# DWM.net
KiCad netlist of a schematic drawn in Altium Designer
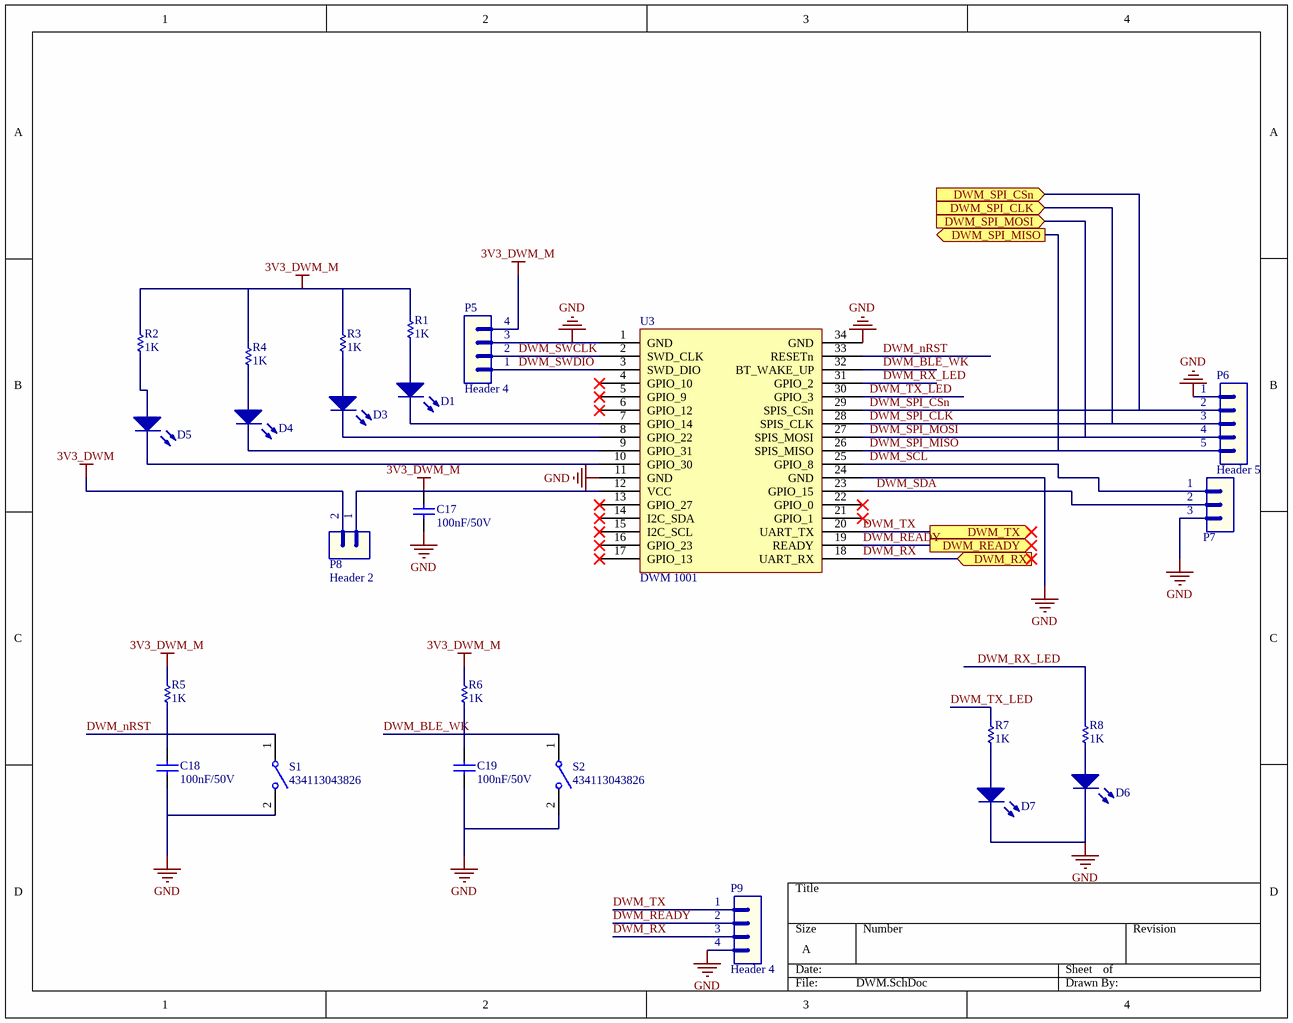
[diagram p0: DWM.SchDoc]

(export (version "E")
  (design (tool "Eeschema 10.0.6"))
  (components
    (comp (ref "C17")
      (value "100nF/50V")
      (footprint "CAP-SM-0805")
      (description "CAP CER 0.1UF 50V Y5V 0805")
      (fields
        (field (name "MANUFACTURER") "Samsung Electro-Mechanics")
        (field (name "MANUFACTURER PART NUMBER") "CL21F104ZBCNNNC")
      )
      (libsource (lib "Capacitor") (part "Cap-100nF-50V-0805"))
    )
    (comp (ref "C18")
      (value "100nF/50V")
      (footprint "CAP-SM-0805")
      (description "CAP CER 0.1UF 50V Y5V 0805")
      (fields
        (field (name "MANUFACTURER") "Samsung Electro-Mechanics")
        (field (name "MANUFACTURER PART NUMBER") "CL21F104ZBCNNNC")
      )
      (libsource (lib "Capacitor") (part "Cap-100nF-50V-0805"))
    )
    (comp (ref "C19")
      (value "100nF/50V")
      (footprint "CAP-SM-0805")
      (description "CAP CER 0.1UF 50V Y5V 0805")
      (fields
        (field (name "MANUFACTURER") "Samsung Electro-Mechanics")
        (field (name "MANUFACTURER PART NUMBER") "CL21F104ZBCNNNC")
      )
      (libsource (lib "Capacitor") (part "Cap-100nF-50V-0805"))
    )
    (comp (ref "D1")
      (value "LED")
      (footprint "LED_0805_Blue")
      (libsource (lib "PIF_C16_lib (1)") (part "LED"))
    )
    (comp (ref "D3")
      (value "LED")
      (footprint "LED_0805_Blue")
      (libsource (lib "PIF_C16_lib (1)") (part "LED"))
    )
    (comp (ref "D4")
      (value "LED")
      (footprint "LED_0805_Blue")
      (libsource (lib "PIF_C16_lib (1)") (part "LED"))
    )
    (comp (ref "D5")
      (value "LED")
      (footprint "LED_0805_Blue")
      (libsource (lib "PIF_C16_lib (1)") (part "LED"))
    )
    (comp (ref "D6")
      (value "LED")
      (footprint "LED_0805_Blue")
      (libsource (lib "PIF_C16_lib (1)") (part "LED"))
    )
    (comp (ref "D7")
      (value "LED")
      (footprint "LED_0805_Blue")
      (libsource (lib "PIF_C16_lib (1)") (part "LED"))
    )
    (comp (ref "P5")
      (value "Header 4")
      (footprint "JP4")
      (description "Header, 4-Pin")
      (fields (field (name "PUBLISHER") "Altium Limited"))
      (libsource (lib "") (part "Header 4_1"))
    )
    (comp (ref "P6")
      (value "Header 5")
      (footprint "JP5")
      (description "Header, 5-Pin")
      (fields (field (name "PUBLISHER") "Altium Limited"))
      (libsource (lib "Header-connector") (part "Header 5"))
    )
    (comp (ref "P7")
      (value "Header 3")
      (footprint "JP3")
      (description "Header, 3-Pin")
      (fields (field (name "PUBLISHER") "Altium Limited"))
      (libsource (lib "Header-connector") (part "Header 3"))
    )
    (comp (ref "P8")
      (value "Header 2")
      (footprint "JP2")
      (description "Header, 2-Pin")
      (fields (field (name "PUBLISHER") "Altium Limited"))
      (libsource (lib "Header-connector") (part "Header 2"))
    )
    (comp (ref "P9")
      (value "Header 4")
      (footprint "JP4")
      (description "Header, 4-Pin")
      (fields (field (name "PUBLISHER") "Altium Limited"))
      (libsource (lib "Header-connector") (part "Header 4"))
    )
    (comp (ref "R1")
      (value "1K")
      (footprint "RES-SM-0805")
      (fields (field (name "Comment") "Resistor 1/4W"))
      (libsource (lib "PIF_C16_lib (1)") (part "RES"))
    )
    (comp (ref "R2")
      (value "1K")
      (footprint "RES-SM-0805")
      (fields (field (name "Comment") "Resistor 1/4W"))
      (libsource (lib "PIF_C16_lib (1)") (part "RES"))
    )
    (comp (ref "R3")
      (value "1K")
      (footprint "RES-SM-0805")
      (fields (field (name "Comment") "Resistor 1/4W"))
      (libsource (lib "PIF_C16_lib (1)") (part "RES"))
    )
    (comp (ref "R4")
      (value "1K")
      (footprint "RES-SM-0805")
      (fields (field (name "Comment") "Resistor 1/4W"))
      (libsource (lib "PIF_C16_lib (1)") (part "RES"))
    )
    (comp (ref "R5")
      (value "1K")
      (footprint "RES-SM-0805")
      (fields (field (name "Comment") "Resistor 1/4W"))
      (libsource (lib "PIF_C16_lib (1)") (part "RES"))
    )
    (comp (ref "R6")
      (value "1K")
      (footprint "RES-SM-0805")
      (fields (field (name "Comment") "Resistor 1/4W"))
      (libsource (lib "PIF_C16_lib (1)") (part "RES"))
    )
    (comp (ref "R7")
      (value "1K")
      (footprint "RES-SM-0805")
      (fields (field (name "Comment") "Resistor 1/4W"))
      (libsource (lib "PIF_C16_lib (1)") (part "RES"))
    )
    (comp (ref "R8")
      (value "1K")
      (footprint "RES-SM-0805")
      (fields (field (name "Comment") "Resistor 1/4W"))
      (libsource (lib "PIF_C16_lib (1)") (part "RES"))
    )
    (comp (ref "S1")
      (value "434113043826")
      (footprint "434113043826")
      (description "WS-TASV J-Bend SMT Tact Switch 6x3.5mm, height 4.3mm, 260gf")
      (fields (field (name "PUBLISHER") "Wurth Elektronik"))
      (libsource (lib "o75727v243 Altium_WS-TASV (rev20a)") (part "434113043826"))
    )
    (comp (ref "S2")
      (value "434113043826")
      (footprint "434113043826")
      (description "WS-TASV J-Bend SMT Tact Switch 6x3.5mm, height 4.3mm, 260gf")
      (fields (field (name "PUBLISHER") "Wurth Elektronik"))
      (libsource (lib "o75727v243 Altium_WS-TASV (rev20a)") (part "434113043826"))
    )
    (comp (ref "U3")
      (value "DWM 1001")
      (footprint "DWM1001:PCBComponent_1")
      (libsource (lib "Bai1") (part "DWM 1001"))
    )
  )
  (nets
    (net (code "1") (name "/DWM_BLE_WK") (class "Default")
      (node (ref "C19") (pin "2") (pinfunction "2_2") (pintype "passive"))
      (node (ref "R6") (pin "1") (pintype "passive"))
      (node (ref "S2") (pin "1") (pinfunction "1_1") (pintype "passive"))
      (node (ref "U3") (pin "32") (pinfunction "BT_WAKE_UP_32") (pintype "passive"))
    )
    (net (code "2") (name "/DWM_READY") (class "Default")
      (node (ref "P9") (pin "2") (pinfunction "2_2") (pintype "passive"))
      (node (ref "U3") (pin "19") (pinfunction "READY_19") (pintype "passive"))
    )
    (net (code "3") (name "/DWM_RX") (class "Default")
      (node (ref "P9") (pin "3") (pinfunction "3_3") (pintype "passive"))
      (node (ref "U3") (pin "18") (pinfunction "UART_RX_18") (pintype "passive"))
    )
    (net (code "4") (name "/DWM_RX_LED") (class "Default")
      (node (ref "R8") (pin "2") (pintype "passive"))
      (node (ref "U3") (pin "31") (pinfunction "GPIO_2_31") (pintype "passive"))
    )
    (net (code "5") (name "/DWM_SCL") (class "Default")
      (node (ref "P7") (pin "1") (pinfunction "1_1") (pintype "passive"))
      (node (ref "U3") (pin "25") (pinfunction "GPIO_8_25") (pintype "passive"))
    )
    (net (code "6") (name "/DWM_SDA") (class "Default")
      (node (ref "P7") (pin "2") (pinfunction "2_2") (pintype "passive"))
      (node (ref "U3") (pin "23") (pinfunction "GPIO_15_23") (pintype "passive"))
    )
    (net (code "7") (name "/DWM_SPI_CLK") (class "Default")
      (node (ref "P6") (pin "3") (pinfunction "3_3") (pintype "passive"))
      (node (ref "U3") (pin "28") (pinfunction "SPIS_CLK_28") (pintype "passive"))
    )
    (net (code "8") (name "/DWM_SPI_CSn") (class "Default")
      (node (ref "P6") (pin "2") (pinfunction "2_2") (pintype "passive"))
      (node (ref "U3") (pin "29") (pinfunction "SPIS_CSn_29") (pintype "passive"))
    )
    (net (code "9") (name "/DWM_SPI_MISO") (class "Default")
      (node (ref "P6") (pin "5") (pinfunction "5_5") (pintype "passive"))
      (node (ref "U3") (pin "26") (pinfunction "SPIS_MISO_26") (pintype "passive"))
    )
    (net (code "10") (name "/DWM_SPI_MOSI") (class "Default")
      (node (ref "P6") (pin "4") (pinfunction "4_4") (pintype "passive"))
      (node (ref "U3") (pin "27") (pinfunction "SPIS_MOSI_27") (pintype "passive"))
    )
    (net (code "11") (name "/DWM_SWCLK") (class "Default")
      (node (ref "P5") (pin "2") (pinfunction "2_2") (pintype "passive"))
      (node (ref "U3") (pin "2") (pinfunction "SWD_CLK_2") (pintype "passive"))
    )
    (net (code "12") (name "/DWM_SWDIO") (class "Default")
      (node (ref "P5") (pin "1") (pinfunction "1_1") (pintype "passive"))
      (node (ref "U3") (pin "3") (pinfunction "SWD_DIO_3") (pintype "passive"))
    )
    (net (code "13") (name "/DWM_TX") (class "Default")
      (node (ref "P9") (pin "1") (pinfunction "1_1") (pintype "passive"))
      (node (ref "U3") (pin "20") (pinfunction "UART_TX_20") (pintype "passive"))
    )
    (net (code "14") (name "/DWM_TX_LED") (class "Default")
      (node (ref "R7") (pin "2") (pintype "passive"))
      (node (ref "U3") (pin "30") (pinfunction "GPIO_3_30") (pintype "passive"))
    )
    (net (code "15") (name "/DWM_nRST") (class "Default")
      (node (ref "C18") (pin "2") (pinfunction "2_2") (pintype "passive"))
      (node (ref "R5") (pin "1") (pintype "passive"))
      (node (ref "S1") (pin "1") (pinfunction "1_1") (pintype "passive"))
      (node (ref "U3") (pin "33") (pinfunction "RESETn_33") (pintype "passive"))
    )
    (net (code "16") (name "3V3_DWM") (class "Default")
      (node (ref "P8") (pin "2") (pinfunction "2_2") (pintype "passive"))
    )
    (net (code "17") (name "3V3_DWM_M") (class "Default")
      (node (ref "C17") (pin "2") (pinfunction "2_2") (pintype "passive"))
      (node (ref "P5") (pin "4") (pinfunction "4_4") (pintype "passive"))
      (node (ref "P8") (pin "1") (pinfunction "1_1") (pintype "passive"))
      (node (ref "R1") (pin "2") (pintype "passive"))
      (node (ref "R2") (pin "2") (pintype "passive"))
      (node (ref "R3") (pin "2") (pintype "passive"))
      (node (ref "R4") (pin "2") (pintype "passive"))
      (node (ref "R5") (pin "2") (pintype "passive"))
      (node (ref "R6") (pin "2") (pintype "passive"))
      (node (ref "U3") (pin "12") (pinfunction "VCC_12") (pintype "passive"))
    )
    (net (code "18") (name "GND") (class "Default")
      (node (ref "C17") (pin "1") (pinfunction "1_1") (pintype "passive"))
      (node (ref "C18") (pin "1") (pinfunction "1_1") (pintype "passive"))
      (node (ref "C19") (pin "1") (pinfunction "1_1") (pintype "passive"))
      (node (ref "D6") (pin "2") (pinfunction "K_2") (pintype "passive"))
      (node (ref "D7") (pin "2") (pinfunction "K_2") (pintype "passive"))
      (node (ref "P5") (pin "3") (pinfunction "3_3") (pintype "passive"))
      (node (ref "P6") (pin "1") (pinfunction "1_1") (pintype "passive"))
      (node (ref "P7") (pin "3") (pinfunction "3_3") (pintype "passive"))
      (node (ref "P9") (pin "4") (pinfunction "4_4") (pintype "passive"))
      (node (ref "S1") (pin "2") (pinfunction "2_2") (pintype "passive"))
      (node (ref "S2") (pin "2") (pinfunction "2_2") (pintype "passive"))
      (node (ref "U3") (pin "1") (pinfunction "GND_1") (pintype "passive"))
      (node (ref "U3") (pin "11") (pinfunction "GND_11") (pintype "passive"))
      (node (ref "U3") (pin "24") (pinfunction "GND_24") (pintype "passive"))
      (node (ref "U3") (pin "34") (pinfunction "GND_34") (pintype "passive"))
    )
    (net (code "19") (name "Net-(D1-A)") (class "Default")
      (node (ref "D1") (pin "1") (pinfunction "A_1") (pintype "passive"))
      (node (ref "R1") (pin "1") (pintype "passive"))
    )
    (net (code "20") (name "Net-(D1-K)") (class "Default")
      (node (ref "D1") (pin "2") (pinfunction "K_2") (pintype "passive"))
      (node (ref "U3") (pin "7") (pinfunction "GPIO_14_7") (pintype "passive"))
    )
    (net (code "21") (name "Net-(D3-A)") (class "Default")
      (node (ref "D3") (pin "1") (pinfunction "A_1") (pintype "passive"))
      (node (ref "R3") (pin "1") (pintype "passive"))
    )
    (net (code "22") (name "Net-(D3-K)") (class "Default")
      (node (ref "D3") (pin "2") (pinfunction "K_2") (pintype "passive"))
      (node (ref "U3") (pin "8") (pinfunction "GPIO_22_8") (pintype "passive"))
    )
    (net (code "23") (name "Net-(D4-A)") (class "Default")
      (node (ref "D4") (pin "1") (pinfunction "A_1") (pintype "passive"))
      (node (ref "R4") (pin "1") (pintype "passive"))
    )
    (net (code "24") (name "Net-(D4-K)") (class "Default")
      (node (ref "D4") (pin "2") (pinfunction "K_2") (pintype "passive"))
      (node (ref "U3") (pin "9") (pinfunction "GPIO_31_9") (pintype "passive"))
    )
    (net (code "25") (name "Net-(D5-A)") (class "Default")
      (node (ref "D5") (pin "1") (pinfunction "A_1") (pintype "passive"))
      (node (ref "R2") (pin "1") (pintype "passive"))
    )
    (net (code "26") (name "Net-(D5-K)") (class "Default")
      (node (ref "D5") (pin "2") (pinfunction "K_2") (pintype "passive"))
      (node (ref "U3") (pin "10") (pinfunction "GPIO_30_10") (pintype "passive"))
    )
    (net (code "27") (name "Net-(D6-A)") (class "Default")
      (node (ref "D6") (pin "1") (pinfunction "A_1") (pintype "passive"))
      (node (ref "R8") (pin "1") (pintype "passive"))
    )
    (net (code "28") (name "Net-(D7-A)") (class "Default")
      (node (ref "D7") (pin "1") (pinfunction "A_1") (pintype "passive"))
      (node (ref "R7") (pin "1") (pintype "passive"))
    )
    (net (code "29") (name "unconnected-(U3-GPIO_0-Pad22)") (class "Default")
      (node (ref "U3") (pin "22") (pinfunction "GPIO_0_22") (pintype "passive+no_connect"))
    )
    (net (code "30") (name "unconnected-(U3-GPIO_1-Pad21)") (class "Default")
      (node (ref "U3") (pin "21") (pinfunction "GPIO_1_21") (pintype "passive+no_connect"))
    )
    (net (code "31") (name "unconnected-(U3-GPIO_9-Pad5)") (class "Default")
      (node (ref "U3") (pin "5") (pinfunction "GPIO_9_5") (pintype "passive+no_connect"))
    )
    (net (code "32") (name "unconnected-(U3-GPIO_10-Pad4)") (class "Default")
      (node (ref "U3") (pin "4") (pinfunction "GPIO_10_4") (pintype "passive+no_connect"))
    )
    (net (code "33") (name "unconnected-(U3-GPIO_12-Pad6)") (class "Default")
      (node (ref "U3") (pin "6") (pinfunction "GPIO_12_6") (pintype "passive+no_connect"))
    )
    (net (code "34") (name "unconnected-(U3-GPIO_13-Pad17)") (class "Default")
      (node (ref "U3") (pin "17") (pinfunction "GPIO_13_17") (pintype "passive+no_connect"))
    )
    (net (code "35") (name "unconnected-(U3-GPIO_23-Pad16)") (class "Default")
      (node (ref "U3") (pin "16") (pinfunction "GPIO_23_16") (pintype "passive+no_connect"))
    )
    (net (code "36") (name "unconnected-(U3-GPIO_27-Pad13)") (class "Default")
      (node (ref "U3") (pin "13") (pinfunction "GPIO_27_13") (pintype "passive+no_connect"))
    )
    (net (code "37") (name "unconnected-(U3-I2C_SCL-Pad15)") (class "Default")
      (node (ref "U3") (pin "15") (pinfunction "I2C_SCL_15") (pintype "passive+no_connect"))
    )
    (net (code "38") (name "unconnected-(U3-I2C_SDA-Pad14)") (class "Default")
      (node (ref "U3") (pin "14") (pinfunction "I2C_SDA_14") (pintype "passive+no_connect"))
    )
  )
)
